# digitalky2.net
KiCad netlist of a schematic drawn in EAGLE
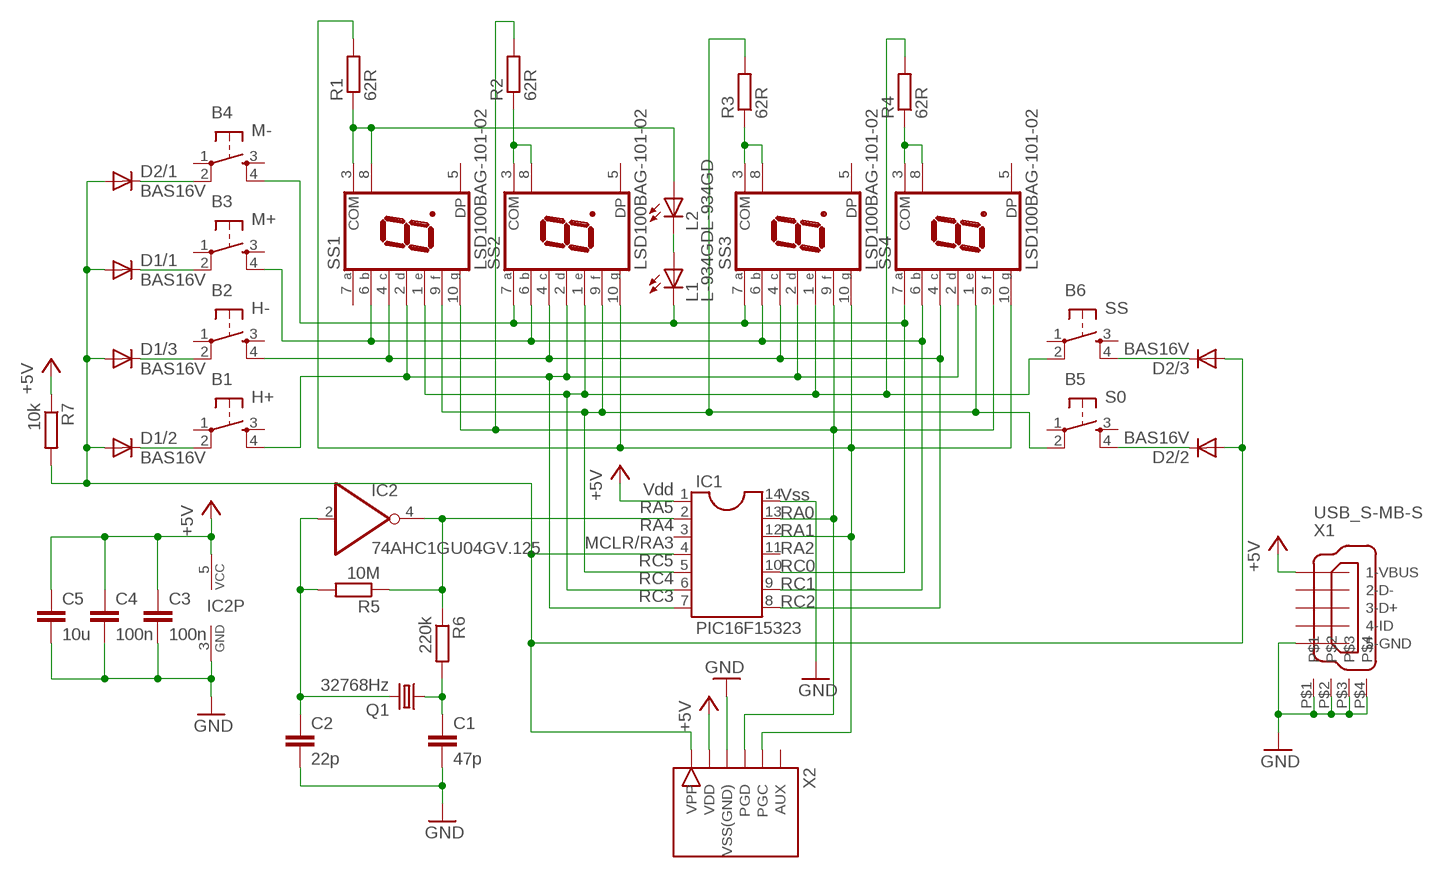
[diagram p0: schematic, sheet 1]

(export (version "E")
  (design (tool "Eeschema 10.0.6"))
  (components
    (comp (ref "B1")
      (value "H+")
      (footprint "eagle-import:TD-03")
      (libsource (lib "eagle-import") (part "TD-03"))
    )
    (comp (ref "B2")
      (value "H-")
      (footprint "eagle-import:TD-03")
      (libsource (lib "eagle-import") (part "TD-03"))
    )
    (comp (ref "B3")
      (value "M+")
      (footprint "eagle-import:TD-03")
      (libsource (lib "eagle-import") (part "TD-03"))
    )
    (comp (ref "B4")
      (value "M-")
      (footprint "eagle-import:TD-03")
      (libsource (lib "eagle-import") (part "TD-03"))
    )
    (comp (ref "B5")
      (value "S0")
      (footprint "eagle-import:TD-03")
      (libsource (lib "eagle-import") (part "TD-03"))
    )
    (comp (ref "B6")
      (value "SS")
      (footprint "eagle-import:TD-03")
      (libsource (lib "eagle-import") (part "TD-03"))
    )
    (comp (ref "C1")
      (value "47p")
      (footprint "eagle-import:C0805")
      (libsource (lib "eagle-import") (part "C-EUC0805"))
    )
    (comp (ref "C2")
      (value "22p")
      (footprint "eagle-import:C0805")
      (libsource (lib "eagle-import") (part "C-EUC0805"))
    )
    (comp (ref "C3")
      (value "100n")
      (footprint "eagle-import:C0805")
      (libsource (lib "eagle-import") (part "C-EUC0805"))
    )
    (comp (ref "C4")
      (value "100n")
      (footprint "eagle-import:C0805")
      (libsource (lib "eagle-import") (part "C-EUC0805"))
    )
    (comp (ref "C5")
      (value "10u")
      (footprint "eagle-import:C1206")
      (libsource (lib "eagle-import") (part "C-EUC1206"))
    )
    (comp (ref "D1")
      (value "BAS16V")
      (footprint "eagle-import:SOT363")
      (libsource (lib "eagle-import") (part "BAS16V"))
    )
    (comp (ref "D2")
      (value "BAS16V")
      (footprint "eagle-import:SOT363")
      (libsource (lib "eagle-import") (part "BAS16V"))
    )
    (comp (ref "IC1")
      (value "PIC16F15323")
      (footprint "eagle-import:SO-14")
      (libsource (lib "eagle-import") (part "DIL14_SMD"))
    )
    (comp (ref "IC2")
      (value "74AHC1GU04GV.125")
      (footprint "eagle-import:SOT23-5")
      (libsource (lib "eagle-import") (part "741G04DBVAHC"))
    )
    (comp (ref "L1")
      (value "L-934GD")
      (footprint "eagle-import:LED3MM")
      (libsource (lib "eagle-import") (part "LED3MM"))
    )
    (comp (ref "L2")
      (value "L-934GD")
      (footprint "eagle-import:LED3MM")
      (libsource (lib "eagle-import") (part "LED3MM"))
    )
    (comp (ref "Q1")
      (value "32768Hz")
      (footprint "eagle-import:TC38H")
      (libsource (lib "eagle-import") (part "CRYSTALTC38H"))
    )
    (comp (ref "R1")
      (value "62R")
      (footprint "eagle-import:R0805")
      (libsource (lib "eagle-import") (part "R-EU_R0805"))
    )
    (comp (ref "R2")
      (value "62R")
      (footprint "eagle-import:R0805")
      (libsource (lib "eagle-import") (part "R-EU_R0805"))
    )
    (comp (ref "R3")
      (value "62R")
      (footprint "eagle-import:R0805")
      (libsource (lib "eagle-import") (part "R-EU_R0805"))
    )
    (comp (ref "R4")
      (value "62R")
      (footprint "eagle-import:R0805")
      (libsource (lib "eagle-import") (part "R-EU_R0805"))
    )
    (comp (ref "R5")
      (value "10M")
      (footprint "eagle-import:R0805")
      (libsource (lib "eagle-import") (part "R-EU_R0805"))
    )
    (comp (ref "R6")
      (value "220k")
      (footprint "eagle-import:R0805")
      (libsource (lib "eagle-import") (part "R-EU_R0805"))
    )
    (comp (ref "R7")
      (value "10k")
      (footprint "eagle-import:R0805")
      (libsource (lib "eagle-import") (part "R-EU_R0805"))
    )
    (comp (ref "SS1")
      (value "LSD100BAG-101-02")
      (footprint "eagle-import:SA10-21-R")
      (libsource (lib "eagle-import") (part "7-SEG_SA10-21-R"))
    )
    (comp (ref "SS2")
      (value "LSD100BAG-101-02")
      (footprint "eagle-import:SA10-21-R")
      (libsource (lib "eagle-import") (part "7-SEG_SA10-21-R"))
    )
    (comp (ref "SS3")
      (value "LSD100BAG-101-02")
      (footprint "eagle-import:SA10-21-R")
      (libsource (lib "eagle-import") (part "7-SEG_SA10-21-R"))
    )
    (comp (ref "SS4")
      (value "LSD100BAG-101-02")
      (footprint "eagle-import:SA10-21-R")
      (libsource (lib "eagle-import") (part "7-SEG_SA10-21-R"))
    )
    (comp (ref "X1")
      (value "USB_S-MB-S")
      (footprint "eagle-import:USB-MB-S")
      (libsource (lib "eagle-import") (part "USB_S-MB-S"))
    )
    (comp (ref "X2")
      (value "PICKITXS")
      (footprint "eagle-import:6PIN3")
      (libsource (lib "eagle-import") (part "PICKITXS"))
    )
  )
  (nets
    (net (code "1") (name "+5V") (class "Default")
      (node (ref "C3") (pin "1") (pinfunction "1_1") (pintype "passive"))
      (node (ref "C4") (pin "1") (pinfunction "1_1") (pintype "passive"))
      (node (ref "C5") (pin "1") (pinfunction "1_1") (pintype "passive"))
      (node (ref "IC1") (pin "1") (pinfunction "1_1") (pintype "passive"))
      (node (ref "IC2") (pin "5") (pinfunction "VCC_5") (pintype "power_in"))
      (node (ref "R7") (pin "1") (pinfunction "1_1") (pintype "passive"))
      (node (ref "X1") (pin "VBUS") (pinfunction "1-VBUS_VBUS") (pintype "input"))
      (node (ref "X2") (pin "P$2") (pinfunction "VDD_P$2") (pintype "bidirectional"))
    )
    (net (code "2") (name "GND") (class "Default")
      (node (ref "C1") (pin "2") (pinfunction "2_2") (pintype "passive"))
      (node (ref "C2") (pin "2") (pinfunction "2_2") (pintype "passive"))
      (node (ref "C3") (pin "2") (pinfunction "2_2") (pintype "passive"))
      (node (ref "C4") (pin "2") (pinfunction "2_2") (pintype "passive"))
      (node (ref "C5") (pin "2") (pinfunction "2_2") (pintype "passive"))
      (node (ref "IC1") (pin "14") (pinfunction "14_14") (pintype "passive"))
      (node (ref "IC2") (pin "3") (pinfunction "GND_3") (pintype "power_in"))
      (node (ref "X1") (pin "GND") (pinfunction "5-GND_GND") (pintype "input"))
      (node (ref "X1") (pin "P$1") (pinfunction "P$1_P$1") (pintype "passive"))
      (node (ref "X1") (pin "P$2") (pinfunction "P$2_P$2") (pintype "passive"))
      (node (ref "X1") (pin "P$3") (pinfunction "P$3_P$3") (pintype "passive"))
      (node (ref "X1") (pin "P$4") (pinfunction "P$4_P$4") (pintype "passive"))
      (node (ref "X2") (pin "P$3") (pinfunction "VSS(GND)_P$3") (pintype "bidirectional"))
    )
    (net (code "3") (name "Net-(C1-Pad1)") (class "Default")
      (node (ref "C1") (pin "1") (pinfunction "1_1") (pintype "passive"))
      (node (ref "Q1") (pin "1") (pinfunction "1_1") (pintype "passive"))
      (node (ref "R6") (pin "2") (pinfunction "2_2") (pintype "passive"))
    )
    (net (code "4") (name "Net-(D1A-A)") (class "Default")
      (node (ref "D1") (pin "1") (pinfunction "A_1") (pintype "passive"))
      (node (ref "D1") (pin "2") (pinfunction "A_2") (pintype "passive"))
      (node (ref "D1") (pin "3") (pinfunction "A_3") (pintype "passive"))
      (node (ref "D2") (pin "1") (pinfunction "A_1") (pintype "passive"))
      (node (ref "D2") (pin "2") (pinfunction "A_2") (pintype "passive"))
      (node (ref "D2") (pin "3") (pinfunction "A_3") (pintype "passive"))
      (node (ref "IC1") (pin "4") (pinfunction "4_4") (pintype "passive"))
      (node (ref "R7") (pin "2") (pinfunction "2_2") (pintype "passive"))
      (node (ref "X2") (pin "P$1") (pinfunction "VPP_P$1") (pintype "bidirectional"))
    )
    (net (code "5") (name "Net-(D1A-C)") (class "Default")
      (node (ref "B3") (pin "2") (pinfunction "2_2") (pintype "passive"))
      (node (ref "D1") (pin "6") (pinfunction "C_6") (pintype "passive"))
    )
    (net (code "6") (name "Net-(D1B-C)") (class "Default")
      (node (ref "B1") (pin "2") (pinfunction "2_2") (pintype "passive"))
      (node (ref "D1") (pin "5") (pinfunction "C_5") (pintype "passive"))
    )
    (net (code "7") (name "Net-(D1C-C)") (class "Default")
      (node (ref "B2") (pin "2") (pinfunction "2_2") (pintype "passive"))
      (node (ref "D1") (pin "4") (pinfunction "C_4") (pintype "passive"))
    )
    (net (code "8") (name "Net-(D2A-C)") (class "Default")
      (node (ref "B4") (pin "2") (pinfunction "2_2") (pintype "passive"))
      (node (ref "D2") (pin "6") (pinfunction "C_6") (pintype "passive"))
    )
    (net (code "9") (name "Net-(D2B-C)") (class "Default")
      (node (ref "B5") (pin "4") (pinfunction "4_4") (pintype "passive"))
      (node (ref "D2") (pin "5") (pinfunction "C_5") (pintype "passive"))
    )
    (net (code "10") (name "Net-(D2C-C)") (class "Default")
      (node (ref "B6") (pin "4") (pinfunction "4_4") (pintype "passive"))
      (node (ref "D2") (pin "4") (pinfunction "C_4") (pintype "passive"))
    )
    (net (code "11") (name "Net-(IC2A-I)") (class "Default")
      (node (ref "C2") (pin "1") (pinfunction "1_1") (pintype "passive"))
      (node (ref "IC2") (pin "2") (pinfunction "I_2") (pintype "input"))
      (node (ref "Q1") (pin "2") (pinfunction "2_2") (pintype "passive"))
      (node (ref "R5") (pin "2") (pinfunction "2_2") (pintype "passive"))
    )
    (net (code "12") (name "Net-(IC2A-O)") (class "Default")
      (node (ref "IC1") (pin "2") (pinfunction "2_2") (pintype "passive"))
      (node (ref "IC2") (pin "4") (pinfunction "O_4") (pintype "output"))
      (node (ref "R5") (pin "1") (pinfunction "1_1") (pintype "passive"))
      (node (ref "R6") (pin "1") (pinfunction "1_1") (pintype "passive"))
    )
    (net (code "13") (name "Net-(L1-C)") (class "Default")
      (node (ref "B4") (pin "4") (pinfunction "4_4") (pintype "passive"))
      (node (ref "IC1") (pin "10") (pinfunction "10_10") (pintype "passive"))
      (node (ref "L1") (pin "K") (pinfunction "C_K") (pintype "passive"))
      (node (ref "SS2") (pin "7") (pinfunction "A_7") (pintype "passive"))
      (node (ref "SS3") (pin "7") (pinfunction "A_7") (pintype "passive"))
      (node (ref "SS4") (pin "7") (pinfunction "A_7") (pintype "passive"))
    )
    (net (code "14") (name "Net-(L2-C)") (class "Default")
      (node (ref "L1") (pin "A") (pinfunction "A_A") (pintype "passive"))
      (node (ref "L2") (pin "K") (pinfunction "C_K") (pintype "passive"))
    )
    (net (code "15") (name "Net-(L2-PadA)") (class "Default")
      (node (ref "L2") (pin "A") (pinfunction "A_A") (pintype "passive"))
      (node (ref "R1") (pin "1") (pinfunction "1_1") (pintype "passive"))
      (node (ref "SS1") (pin "3") (pinfunction "COM_3") (pintype "passive"))
      (node (ref "SS1") (pin "8") (pinfunction "COM_8") (pintype "passive"))
    )
    (net (code "16") (name "Net-(R2-Pad1)") (class "Default")
      (node (ref "R2") (pin "1") (pinfunction "1_1") (pintype "passive"))
      (node (ref "SS2") (pin "3") (pinfunction "COM_3") (pintype "passive"))
      (node (ref "SS2") (pin "8") (pinfunction "COM_8") (pintype "passive"))
    )
    (net (code "17") (name "Net-(R3-Pad1)") (class "Default")
      (node (ref "R3") (pin "1") (pinfunction "1_1") (pintype "passive"))
      (node (ref "SS3") (pin "3") (pinfunction "COM_3") (pintype "passive"))
      (node (ref "SS3") (pin "8") (pinfunction "COM_8") (pintype "passive"))
    )
    (net (code "18") (name "Net-(R4-Pad1)") (class "Default")
      (node (ref "R4") (pin "1") (pinfunction "1_1") (pintype "passive"))
      (node (ref "SS4") (pin "3") (pinfunction "COM_3") (pintype "passive"))
      (node (ref "SS4") (pin "8") (pinfunction "COM_8") (pintype "passive"))
    )
    (net (code "19") (name "Net-(SS1-B)") (class "Default")
      (node (ref "B3") (pin "4") (pinfunction "4_4") (pintype "passive"))
      (node (ref "IC1") (pin "9") (pinfunction "9_9") (pintype "passive"))
      (node (ref "SS1") (pin "6") (pinfunction "B_6") (pintype "passive"))
      (node (ref "SS2") (pin "6") (pinfunction "B_6") (pintype "passive"))
      (node (ref "SS3") (pin "6") (pinfunction "B_6") (pintype "passive"))
      (node (ref "SS4") (pin "6") (pinfunction "B_6") (pintype "passive"))
    )
    (net (code "20") (name "Net-(SS1-C)") (class "Default")
      (node (ref "B2") (pin "4") (pinfunction "4_4") (pintype "passive"))
      (node (ref "IC1") (pin "8") (pinfunction "8_8") (pintype "passive"))
      (node (ref "SS1") (pin "4") (pinfunction "C_4") (pintype "passive"))
      (node (ref "SS2") (pin "4") (pinfunction "C_4") (pintype "passive"))
      (node (ref "SS3") (pin "4") (pinfunction "C_4") (pintype "passive"))
      (node (ref "SS4") (pin "4") (pinfunction "C_4") (pintype "passive"))
    )
    (net (code "21") (name "Net-(SS1-D)") (class "Default")
      (node (ref "B1") (pin "4") (pinfunction "4_4") (pintype "passive"))
      (node (ref "IC1") (pin "7") (pinfunction "7_7") (pintype "passive"))
      (node (ref "SS1") (pin "2") (pinfunction "D_2") (pintype "passive"))
      (node (ref "SS2") (pin "2") (pinfunction "D_2") (pintype "passive"))
      (node (ref "SS3") (pin "2") (pinfunction "D_2") (pintype "passive"))
      (node (ref "SS4") (pin "2") (pinfunction "D_2") (pintype "passive"))
    )
    (net (code "22") (name "Net-(SS1-E)") (class "Default")
      (node (ref "B6") (pin "2") (pinfunction "2_2") (pintype "passive"))
      (node (ref "IC1") (pin "6") (pinfunction "6_6") (pintype "passive"))
      (node (ref "R4") (pin "2") (pinfunction "2_2") (pintype "passive"))
      (node (ref "SS1") (pin "1") (pinfunction "E_1") (pintype "passive"))
      (node (ref "SS2") (pin "1") (pinfunction "E_1") (pintype "passive"))
      (node (ref "SS3") (pin "1") (pinfunction "E_1") (pintype "passive"))
    )
    (net (code "23") (name "Net-(SS1-F)") (class "Default")
      (node (ref "B5") (pin "2") (pinfunction "2_2") (pintype "passive"))
      (node (ref "IC1") (pin "5") (pinfunction "5_5") (pintype "passive"))
      (node (ref "R3") (pin "2") (pinfunction "2_2") (pintype "passive"))
      (node (ref "SS1") (pin "9") (pinfunction "F_9") (pintype "passive"))
      (node (ref "SS2") (pin "9") (pinfunction "F_9") (pintype "passive"))
      (node (ref "SS4") (pin "1") (pinfunction "E_1") (pintype "passive"))
    )
    (net (code "24") (name "Net-(SS1-G)") (class "Default")
      (node (ref "IC1") (pin "13") (pinfunction "13_13") (pintype "passive"))
      (node (ref "R2") (pin "2") (pinfunction "2_2") (pintype "passive"))
      (node (ref "SS1") (pin "10") (pinfunction "G_10") (pintype "passive"))
      (node (ref "SS3") (pin "9") (pinfunction "F_9") (pintype "passive"))
      (node (ref "SS4") (pin "9") (pinfunction "F_9") (pintype "passive"))
      (node (ref "X2") (pin "P$4") (pinfunction "PGD_P$4") (pintype "bidirectional"))
    )
    (net (code "25") (name "Net-(SS2-G)") (class "Default")
      (node (ref "IC1") (pin "12") (pinfunction "12_12") (pintype "passive"))
      (node (ref "R1") (pin "2") (pinfunction "2_2") (pintype "passive"))
      (node (ref "SS2") (pin "10") (pinfunction "G_10") (pintype "passive"))
      (node (ref "SS3") (pin "10") (pinfunction "G_10") (pintype "passive"))
      (node (ref "SS4") (pin "10") (pinfunction "G_10") (pintype "passive"))
      (node (ref "X2") (pin "P$5") (pinfunction "PGC_P$5") (pintype "bidirectional"))
    )
    (net (code "26") (name "unconnected-(B1-Pad1)") (class "Default")
      (node (ref "B1") (pin "1") (pinfunction "1_1") (pintype "passive"))
    )
    (net (code "27") (name "unconnected-(B1-Pad3)") (class "Default")
      (node (ref "B1") (pin "3") (pinfunction "3_3") (pintype "passive"))
    )
    (net (code "28") (name "unconnected-(B2-Pad1)") (class "Default")
      (node (ref "B2") (pin "1") (pinfunction "1_1") (pintype "passive"))
    )
    (net (code "29") (name "unconnected-(B2-Pad3)") (class "Default")
      (node (ref "B2") (pin "3") (pinfunction "3_3") (pintype "passive"))
    )
    (net (code "30") (name "unconnected-(B3-Pad1)") (class "Default")
      (node (ref "B3") (pin "1") (pinfunction "1_1") (pintype "passive"))
    )
    (net (code "31") (name "unconnected-(B3-Pad3)") (class "Default")
      (node (ref "B3") (pin "3") (pinfunction "3_3") (pintype "passive"))
    )
    (net (code "32") (name "unconnected-(B4-Pad1)") (class "Default")
      (node (ref "B4") (pin "1") (pinfunction "1_1") (pintype "passive"))
    )
    (net (code "33") (name "unconnected-(B4-Pad3)") (class "Default")
      (node (ref "B4") (pin "3") (pinfunction "3_3") (pintype "passive"))
    )
    (net (code "34") (name "unconnected-(B5-Pad1)") (class "Default")
      (node (ref "B5") (pin "1") (pinfunction "1_1") (pintype "passive"))
    )
    (net (code "35") (name "unconnected-(B5-Pad3)") (class "Default")
      (node (ref "B5") (pin "3") (pinfunction "3_3") (pintype "passive"))
    )
    (net (code "36") (name "unconnected-(B6-Pad1)") (class "Default")
      (node (ref "B6") (pin "1") (pinfunction "1_1") (pintype "passive"))
    )
    (net (code "37") (name "unconnected-(B6-Pad3)") (class "Default")
      (node (ref "B6") (pin "3") (pinfunction "3_3") (pintype "passive"))
    )
    (net (code "38") (name "unconnected-(IC1-Pad3)") (class "Default")
      (node (ref "IC1") (pin "3") (pinfunction "3_3") (pintype "passive"))
    )
    (net (code "39") (name "unconnected-(IC1-Pad11)") (class "Default")
      (node (ref "IC1") (pin "11") (pinfunction "11_11") (pintype "passive"))
    )
    (net (code "40") (name "unconnected-(SS1-A-Pad7)") (class "Default")
      (node (ref "SS1") (pin "7") (pinfunction "A_7") (pintype "passive"))
    )
    (net (code "41") (name "unconnected-(SS1-DP-Pad5)") (class "Default")
      (node (ref "SS1") (pin "5") (pinfunction "DP_5") (pintype "passive"))
    )
    (net (code "42") (name "unconnected-(SS2-DP-Pad5)") (class "Default")
      (node (ref "SS2") (pin "5") (pinfunction "DP_5") (pintype "passive"))
    )
    (net (code "43") (name "unconnected-(SS3-DP-Pad5)") (class "Default")
      (node (ref "SS3") (pin "5") (pinfunction "DP_5") (pintype "passive"))
    )
    (net (code "44") (name "unconnected-(SS4-DP-Pad5)") (class "Default")
      (node (ref "SS4") (pin "5") (pinfunction "DP_5") (pintype "passive"))
    )
    (net (code "45") (name "unconnected-(X1-2-D--PadD-)") (class "Default")
      (node (ref "X1") (pin "D-") (pinfunction "2-D-_D-") (pintype "input"))
    )
    (net (code "46") (name "unconnected-(X1-3-D+-PadD+)") (class "Default")
      (node (ref "X1") (pin "D+") (pinfunction "3-D+_D+") (pintype "input"))
    )
    (net (code "47") (name "unconnected-(X1-4-ID-PadID)") (class "Default")
      (node (ref "X1") (pin "ID") (pinfunction "4-ID_ID") (pintype "input"))
    )
    (net (code "48") (name "unconnected-(X2-AUX-PadP$6)") (class "Default")
      (node (ref "X2") (pin "P$6") (pinfunction "AUX_P$6") (pintype "bidirectional"))
    )
  )
)
